# CM4_Conn.net
KiCad netlist of a schematic drawn in Altium Designer
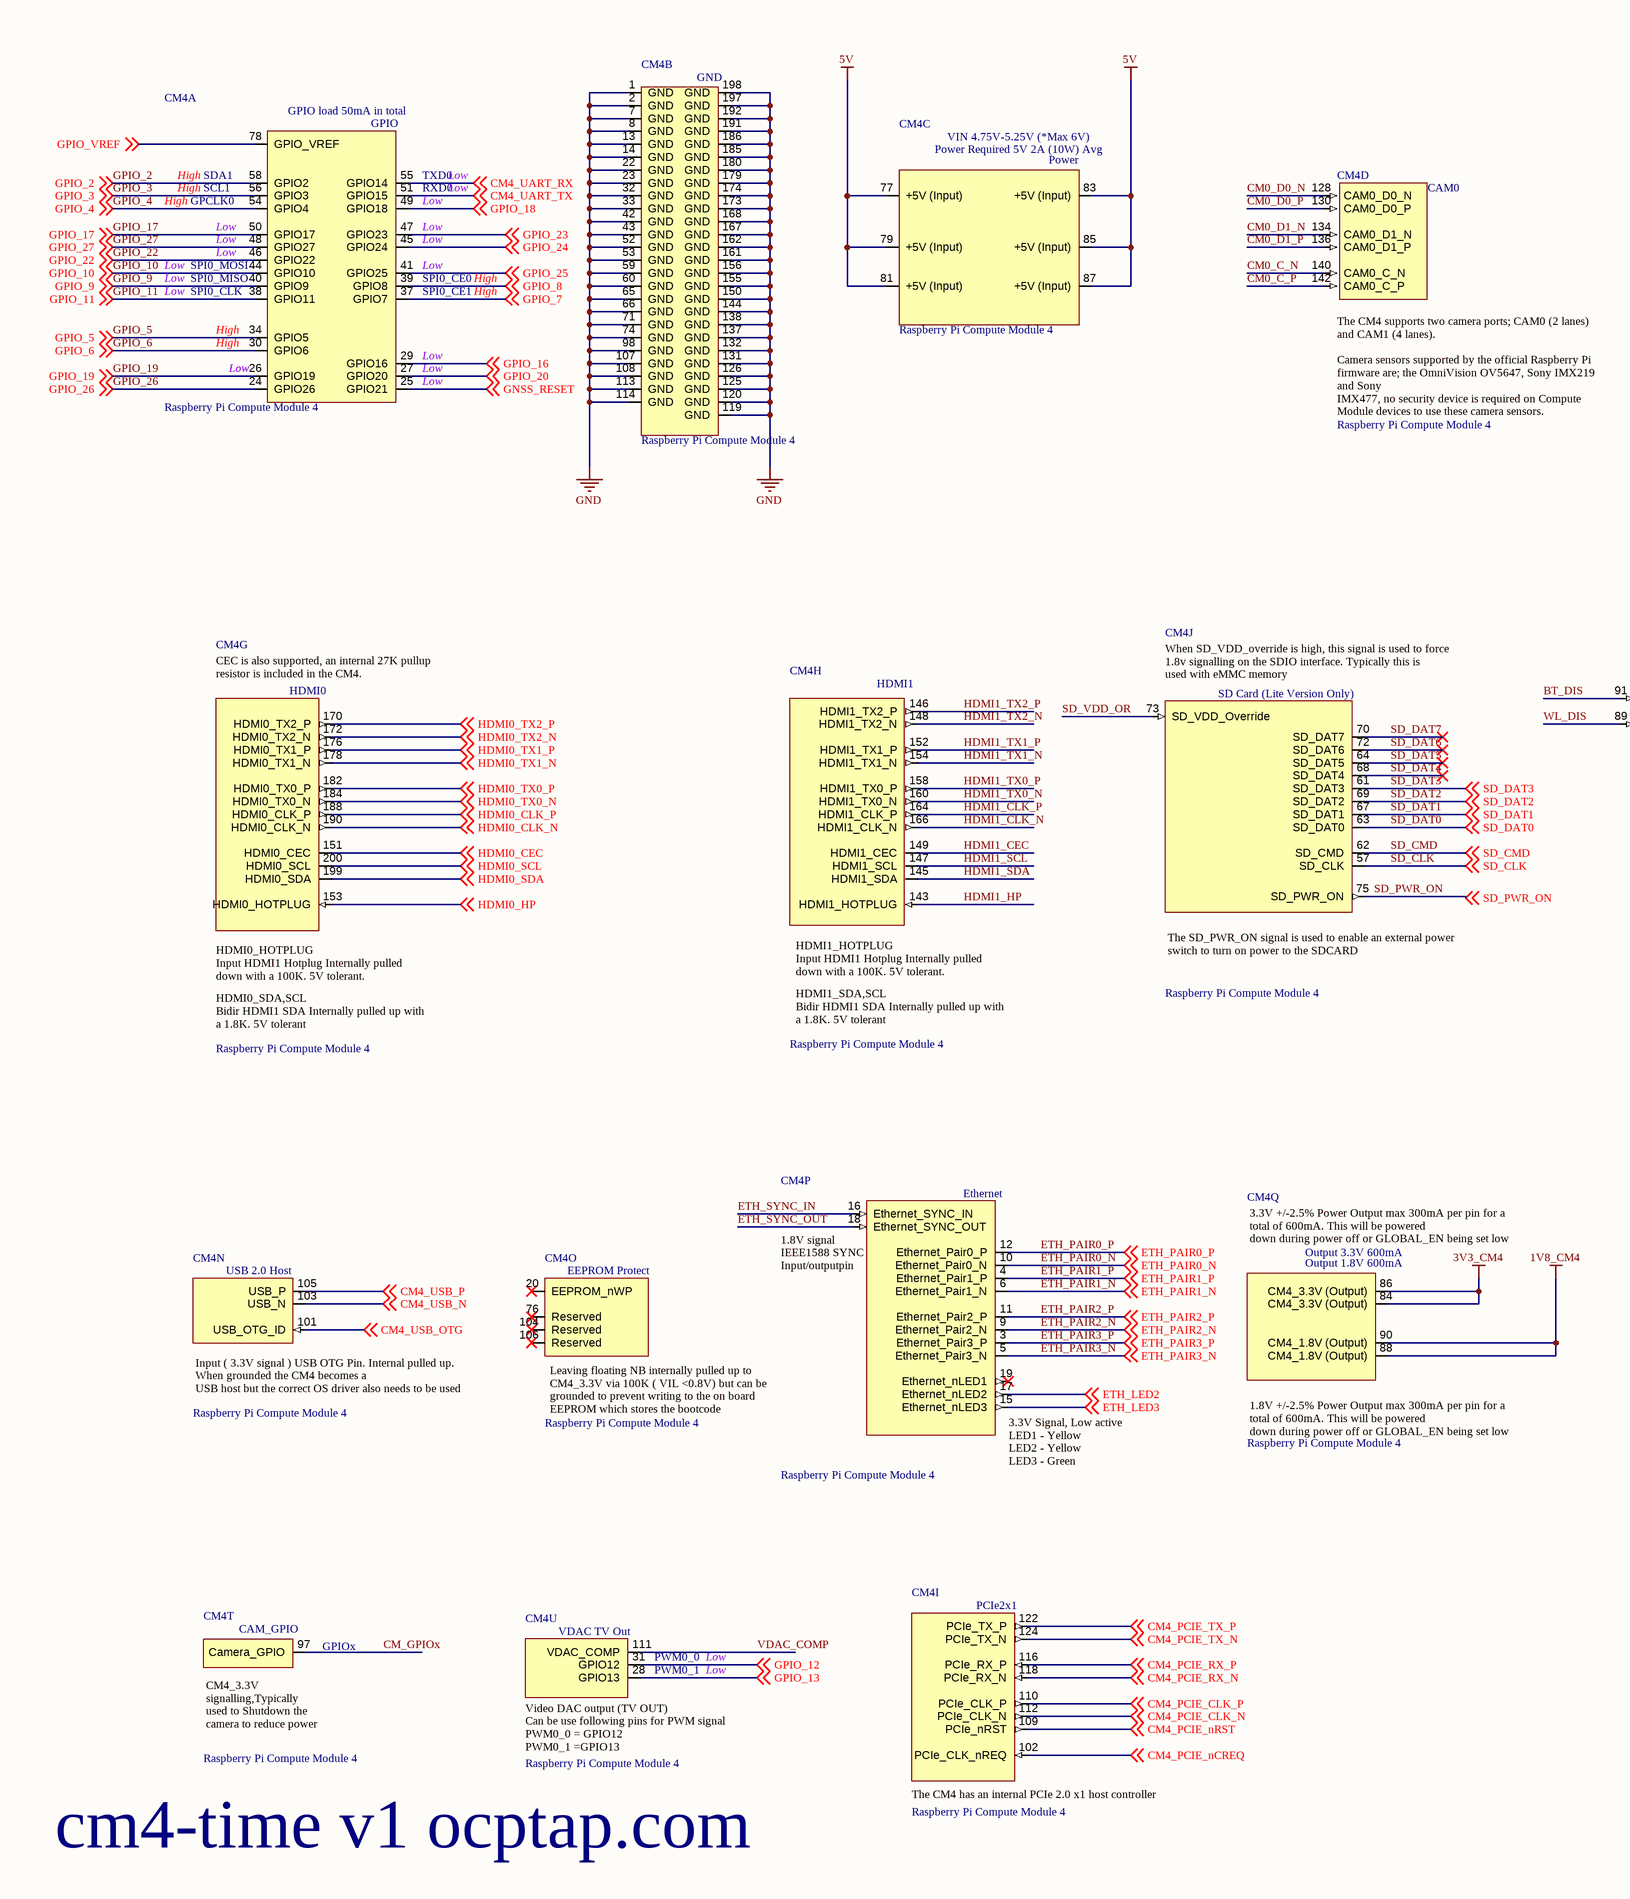
[diagram p0: CM4_Conn.SchDoc, left]
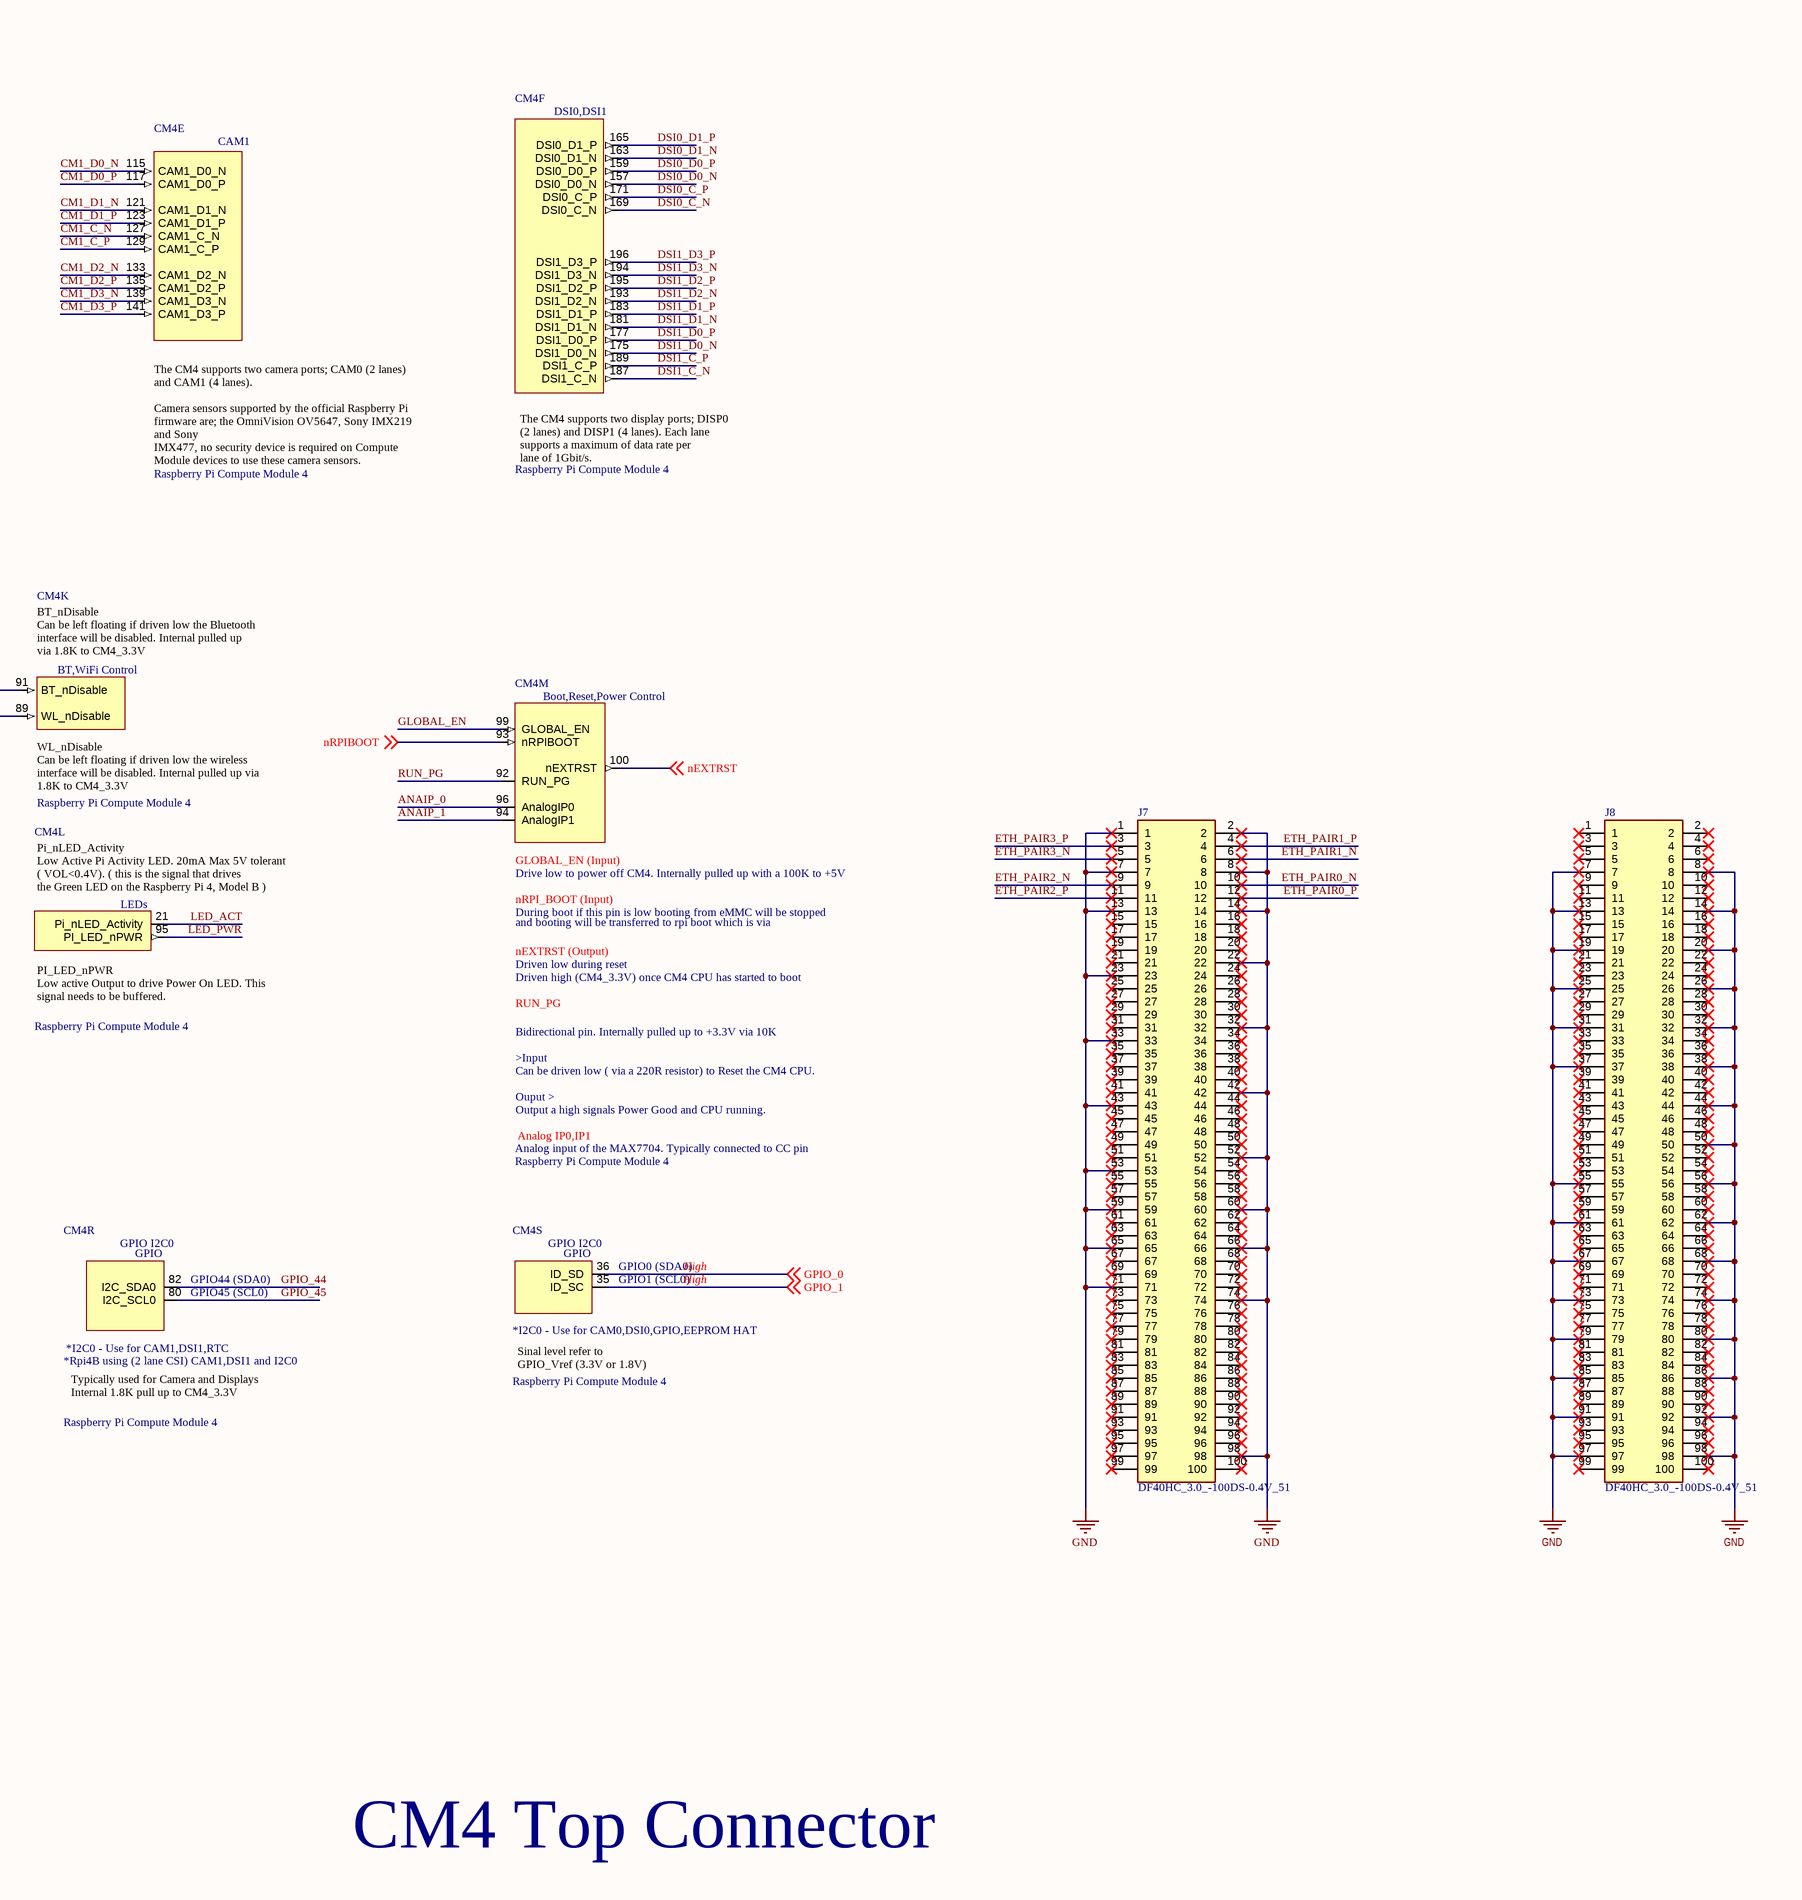
[diagram p1: CM4_Conn.SchDoc, right]

(export (version "E")
  (design (tool "Eeschema 10.0.6"))
  (components
    (comp (ref "CM4")
      (value "Raspberry Pi Compute Module 4")
      (footprint "CM4-F40C-100DS-0.4v_1.5mm_0mm")
      (description "Raspberry Pi Compute Module 4 by Amornthep Phunsin")
      (libsource (lib "CM4") (part "CM4"))
    )
    (comp (ref "J7")
      (value "DF40HC_3.0_-100DS-0.4V_51")
      (footprint "DF40HC30100DS04V51")
      (description "Connector")
      (fields
        (field (name "MANUFACTURER_PART_NUMBER") "DF40HC(3.0)-100DS-0.4V(51")
        (field (name "MOUSER PART NUMBER") "798-DF40HC30100DS451")
      )
      (libsource (lib "SamacSys") (part "DF40HC_3.0_-100DS-0.4V_51"))
    )
    (comp (ref "J8")
      (value "DF40HC_3.0_-100DS-0.4V_51")
      (footprint "DF40HC30100DS04V51")
      (description "Connector")
      (fields
        (field (name "MANUFACTURER_PART_NUMBER") "DF40HC(3.0)-100DS-0.4V(51")
        (field (name "MOUSER PART NUMBER") "798-DF40HC30100DS451")
      )
      (libsource (lib "SamacSys") (part "DF40HC_3.0_-100DS-0.4V_51"))
    )
  )
  (nets
    (net (code "1") (name "/ANAIP_0") (class "Default")
      (node (ref "CM4") (pin "96") (pinfunction "AnalogIP0_96") (pintype "passive"))
    )
    (net (code "2") (name "/ANAIP_1") (class "Default")
      (node (ref "CM4") (pin "94") (pinfunction "AnalogIP1_94") (pintype "passive"))
    )
    (net (code "3") (name "/BT_DIS") (class "Default")
      (node (ref "CM4") (pin "91") (pinfunction "BT_nDisable_91") (pintype "input"))
    )
    (net (code "4") (name "/CM0_C_N") (class "Default")
      (node (ref "CM4") (pin "140") (pinfunction "CAM0_C_N_140") (pintype "input"))
    )
    (net (code "5") (name "/CM0_C_P") (class "Default")
      (node (ref "CM4") (pin "142") (pinfunction "CAM0_C_P_142") (pintype "input"))
    )
    (net (code "6") (name "/CM0_D0_N") (class "Default")
      (node (ref "CM4") (pin "128") (pinfunction "CAM0_D0_N_128") (pintype "input"))
    )
    (net (code "7") (name "/CM0_D0_P") (class "Default")
      (node (ref "CM4") (pin "130") (pinfunction "CAM0_D0_P_130") (pintype "input"))
    )
    (net (code "8") (name "/CM0_D1_N") (class "Default")
      (node (ref "CM4") (pin "134") (pinfunction "CAM0_D1_N_134") (pintype "input"))
    )
    (net (code "9") (name "/CM0_D1_P") (class "Default")
      (node (ref "CM4") (pin "136") (pinfunction "CAM0_D1_P_136") (pintype "input"))
    )
    (net (code "10") (name "/CM1_C_N") (class "Default")
      (node (ref "CM4") (pin "127") (pinfunction "CAM1_C_N_127") (pintype "input"))
    )
    (net (code "11") (name "/CM1_C_P") (class "Default")
      (node (ref "CM4") (pin "129") (pinfunction "CAM1_C_P_129") (pintype "input"))
    )
    (net (code "12") (name "/CM1_D0_N") (class "Default")
      (node (ref "CM4") (pin "115") (pinfunction "CAM1_D0_N_115") (pintype "input"))
    )
    (net (code "13") (name "/CM1_D0_P") (class "Default")
      (node (ref "CM4") (pin "117") (pinfunction "CAM1_D0_P_117") (pintype "input"))
    )
    (net (code "14") (name "/CM1_D1_N") (class "Default")
      (node (ref "CM4") (pin "121") (pinfunction "CAM1_D1_N_121") (pintype "input"))
    )
    (net (code "15") (name "/CM1_D1_P") (class "Default")
      (node (ref "CM4") (pin "123") (pinfunction "CAM1_D1_P_123") (pintype "input"))
    )
    (net (code "16") (name "/CM1_D2_N") (class "Default")
      (node (ref "CM4") (pin "133") (pinfunction "CAM1_D2_N_133") (pintype "input"))
    )
    (net (code "17") (name "/CM1_D2_P") (class "Default")
      (node (ref "CM4") (pin "135") (pinfunction "CAM1_D2_P_135") (pintype "input"))
    )
    (net (code "18") (name "/CM1_D3_N") (class "Default")
      (node (ref "CM4") (pin "139") (pinfunction "CAM1_D3_N_139") (pintype "input"))
    )
    (net (code "19") (name "/CM1_D3_P") (class "Default")
      (node (ref "CM4") (pin "141") (pinfunction "CAM1_D3_P_141") (pintype "input"))
    )
    (net (code "20") (name "/CM_GPIOx") (class "Default")
      (node (ref "CM4") (pin "97") (pinfunction "Camera_GPIO_97") (pintype "passive"))
    )
    (net (code "21") (name "/DSI0_C_N") (class "Default")
      (node (ref "CM4") (pin "169") (pinfunction "DSI0_C_N_169") (pintype "output"))
    )
    (net (code "22") (name "/DSI0_C_P") (class "Default")
      (node (ref "CM4") (pin "171") (pinfunction "DSI0_C_P_171") (pintype "output"))
    )
    (net (code "23") (name "/DSI0_D0_N") (class "Default")
      (node (ref "CM4") (pin "157") (pinfunction "DSI0_D0_N_157") (pintype "output"))
    )
    (net (code "24") (name "/DSI0_D0_P") (class "Default")
      (node (ref "CM4") (pin "159") (pinfunction "DSI0_D0_P_159") (pintype "output"))
    )
    (net (code "25") (name "/DSI0_D1_N") (class "Default")
      (node (ref "CM4") (pin "163") (pinfunction "DSI0_D1_N_163") (pintype "output"))
    )
    (net (code "26") (name "/DSI0_D1_P") (class "Default")
      (node (ref "CM4") (pin "165") (pinfunction "DSI0_D1_P_165") (pintype "output"))
    )
    (net (code "27") (name "/DSI1_C_N") (class "Default")
      (node (ref "CM4") (pin "187") (pinfunction "DSI1_C_N_187") (pintype "output"))
    )
    (net (code "28") (name "/DSI1_C_P") (class "Default")
      (node (ref "CM4") (pin "189") (pinfunction "DSI1_C_P_189") (pintype "output"))
    )
    (net (code "29") (name "/DSI1_D0_N") (class "Default")
      (node (ref "CM4") (pin "175") (pinfunction "DSI1_D0_N_175") (pintype "output"))
    )
    (net (code "30") (name "/DSI1_D0_P") (class "Default")
      (node (ref "CM4") (pin "177") (pinfunction "DSI1_D0_P_177") (pintype "output"))
    )
    (net (code "31") (name "/DSI1_D1_N") (class "Default")
      (node (ref "CM4") (pin "181") (pinfunction "DSI1_D1_N_181") (pintype "output"))
    )
    (net (code "32") (name "/DSI1_D1_P") (class "Default")
      (node (ref "CM4") (pin "183") (pinfunction "DSI1_D1_P_183") (pintype "output"))
    )
    (net (code "33") (name "/DSI1_D2_N") (class "Default")
      (node (ref "CM4") (pin "193") (pinfunction "DSI1_D2_N_193") (pintype "output"))
    )
    (net (code "34") (name "/DSI1_D2_P") (class "Default")
      (node (ref "CM4") (pin "195") (pinfunction "DSI1_D2_P_195") (pintype "output"))
    )
    (net (code "35") (name "/DSI1_D3_N") (class "Default")
      (node (ref "CM4") (pin "194") (pinfunction "DSI1_D3_N_194") (pintype "output"))
    )
    (net (code "36") (name "/DSI1_D3_P") (class "Default")
      (node (ref "CM4") (pin "196") (pinfunction "DSI1_D3_P_196") (pintype "output"))
    )
    (net (code "37") (name "/ETH_SYNC_IN") (class "Default")
      (node (ref "CM4") (pin "16") (pinfunction "Ethernet_SYNC_IN_16") (pintype "input"))
    )
    (net (code "38") (name "/ETH_SYNC_OUT") (class "Default")
      (node (ref "CM4") (pin "18") (pinfunction "Ethernet_SYNC_OUT_18") (pintype "input"))
    )
    (net (code "39") (name "/GLOBAL_EN") (class "Default")
      (node (ref "CM4") (pin "99") (pinfunction "GLOBAL_EN_99") (pintype "input"))
    )
    (net (code "40") (name "/GPIO_44") (class "Default")
      (node (ref "CM4") (pin "82") (pinfunction "I2C_SDA0_82") (pintype "passive"))
    )
    (net (code "41") (name "/GPIO_45") (class "Default")
      (node (ref "CM4") (pin "80") (pinfunction "I2C_SCL0_80") (pintype "passive"))
    )
    (net (code "42") (name "/HDMI1_CEC") (class "Default")
      (node (ref "CM4") (pin "149") (pinfunction "HDMI1_CEC_149") (pintype "open_collector"))
    )
    (net (code "43") (name "/HDMI1_CLK_N") (class "Default")
      (node (ref "CM4") (pin "166") (pinfunction "HDMI1_CLK_N_166") (pintype "output"))
    )
    (net (code "44") (name "/HDMI1_CLK_P") (class "Default")
      (node (ref "CM4") (pin "164") (pinfunction "HDMI1_CLK_P_164") (pintype "output"))
    )
    (net (code "45") (name "/HDMI1_HP") (class "Default")
      (node (ref "CM4") (pin "143") (pinfunction "HDMI1_HOTPLUG_143") (pintype "input"))
    )
    (net (code "46") (name "/HDMI1_SCL") (class "Default")
      (node (ref "CM4") (pin "147") (pinfunction "HDMI1_SCL_147") (pintype "open_collector"))
    )
    (net (code "47") (name "/HDMI1_SDA") (class "Default")
      (node (ref "CM4") (pin "145") (pinfunction "HDMI1_SDA_145") (pintype "bidirectional"))
    )
    (net (code "48") (name "/HDMI1_TX0_N") (class "Default")
      (node (ref "CM4") (pin "160") (pinfunction "HDMI1_TX0_N_160") (pintype "output"))
    )
    (net (code "49") (name "/HDMI1_TX0_P") (class "Default")
      (node (ref "CM4") (pin "158") (pinfunction "HDMI1_TX0_P_158") (pintype "output"))
    )
    (net (code "50") (name "/HDMI1_TX1_N") (class "Default")
      (node (ref "CM4") (pin "154") (pinfunction "HDMI1_TX1_N_154") (pintype "output"))
    )
    (net (code "51") (name "/HDMI1_TX1_P") (class "Default")
      (node (ref "CM4") (pin "152") (pinfunction "HDMI1_TX1_P_152") (pintype "output"))
    )
    (net (code "52") (name "/HDMI1_TX2_N") (class "Default")
      (node (ref "CM4") (pin "148") (pinfunction "HDMI1_TX2_N_148") (pintype "output"))
    )
    (net (code "53") (name "/HDMI1_TX2_P") (class "Default")
      (node (ref "CM4") (pin "146") (pinfunction "HDMI1_TX2_P_146") (pintype "output"))
    )
    (net (code "54") (name "/LED_ACT") (class "Default")
      (node (ref "CM4") (pin "21") (pinfunction "Pi_nLED_Activity_21") (pintype "open_collector"))
    )
    (net (code "55") (name "/LED_PWR") (class "Default")
      (node (ref "CM4") (pin "95") (pinfunction "PI_LED_nPWR_95") (pintype "output"))
    )
    (net (code "56") (name "/RUN_PG") (class "Default")
      (node (ref "CM4") (pin "92") (pinfunction "RUN_PG_92") (pintype "passive"))
    )
    (net (code "57") (name "/SD_DAT4") (class "Default")
      (node (ref "CM4") (pin "68") (pinfunction "SD_DAT4_68") (pintype "passive+no_connect"))
    )
    (net (code "58") (name "/SD_DAT5") (class "Default")
      (node (ref "CM4") (pin "64") (pinfunction "SD_DAT5_64") (pintype "passive+no_connect"))
    )
    (net (code "59") (name "/SD_DAT6") (class "Default")
      (node (ref "CM4") (pin "72") (pinfunction "SD_DAT6_72") (pintype "passive+no_connect"))
    )
    (net (code "60") (name "/SD_DAT7") (class "Default")
      (node (ref "CM4") (pin "70") (pinfunction "SD_DAT7_70") (pintype "passive+no_connect"))
    )
    (net (code "61") (name "/SD_VDD_OR") (class "Default")
      (node (ref "CM4") (pin "73") (pinfunction "SD_VDD_Override_73") (pintype "input"))
    )
    (net (code "62") (name "/VDAC_COMP") (class "Default")
      (node (ref "CM4") (pin "111") (pinfunction "VDAC_COMP_111") (pintype "passive"))
    )
    (net (code "63") (name "/WL_DIS") (class "Default")
      (node (ref "CM4") (pin "89") (pinfunction "WL_nDisable_89") (pintype "input"))
    )
    (net (code "64") (name "1V8_CM4") (class "Default")
      (node (ref "CM4") (pin "88") (pinfunction "CM4_1.8V_(Output)_88") (pintype "power_in"))
      (node (ref "CM4") (pin "90") (pinfunction "CM4_1.8V_(Output)_90") (pintype "power_in"))
    )
    (net (code "65") (name "3V3_CM4") (class "Default")
      (node (ref "CM4") (pin "84") (pinfunction "CM4_3.3V_(Output)_84") (pintype "power_in"))
      (node (ref "CM4") (pin "86") (pinfunction "CM4_3.3V_(Output)_86") (pintype "power_in"))
    )
    (net (code "66") (name "5V") (class "Default")
      (node (ref "CM4") (pin "77") (pinfunction "+5V_(Input)_77") (pintype "power_in"))
      (node (ref "CM4") (pin "79") (pinfunction "+5V_(Input)_79") (pintype "power_in"))
      (node (ref "CM4") (pin "81") (pinfunction "+5V_(Input)_81") (pintype "power_in"))
      (node (ref "CM4") (pin "83") (pinfunction "+5V_(Input)_83") (pintype "power_in"))
      (node (ref "CM4") (pin "85") (pinfunction "+5V_(Input)_85") (pintype "power_in"))
      (node (ref "CM4") (pin "87") (pinfunction "+5V_(Input)_87") (pintype "power_in"))
    )
    (net (code "67") (name "CM4_PCIE_CLK_N") (class "Default")
      (node (ref "CM4") (pin "112") (pinfunction "PCIe_CLK_N_112") (pintype "output"))
    )
    (net (code "68") (name "CM4_PCIE_CLK_P") (class "Default")
      (node (ref "CM4") (pin "110") (pinfunction "PCIe_CLK_P_110") (pintype "output"))
    )
    (net (code "69") (name "CM4_PCIE_RX_N") (class "Default")
      (node (ref "CM4") (pin "118") (pinfunction "PCIe_RX_N_118") (pintype "input"))
    )
    (net (code "70") (name "CM4_PCIE_RX_P") (class "Default")
      (node (ref "CM4") (pin "116") (pinfunction "PCIe_RX_P_116") (pintype "input"))
    )
    (net (code "71") (name "CM4_PCIE_TX_N") (class "Default")
      (node (ref "CM4") (pin "124") (pinfunction "PCIe_TX_N_124") (pintype "output"))
    )
    (net (code "72") (name "CM4_PCIE_TX_P") (class "Default")
      (node (ref "CM4") (pin "122") (pinfunction "PCIe_TX_P_122") (pintype "output"))
    )
    (net (code "73") (name "CM4_PCIE_nCREQ") (class "Default")
      (node (ref "CM4") (pin "102") (pinfunction "PCIe_CLK_nREQ_102") (pintype "input"))
    )
    (net (code "74") (name "CM4_PCIE_nRST") (class "Default")
      (node (ref "CM4") (pin "109") (pinfunction "PCIe_nRST_109") (pintype "output"))
    )
    (net (code "75") (name "CM4_UART_RX") (class "Default")
      (node (ref "CM4") (pin "55") (pinfunction "GPIO14_55") (pintype "passive"))
    )
    (net (code "76") (name "CM4_UART_TX") (class "Default")
      (node (ref "CM4") (pin "51") (pinfunction "GPIO15_51") (pintype "passive"))
    )
    (net (code "77") (name "CM4_USB_N") (class "Default")
      (node (ref "CM4") (pin "103") (pinfunction "USB_N_103") (pintype "passive"))
    )
    (net (code "78") (name "CM4_USB_OTG") (class "Default")
      (node (ref "CM4") (pin "101") (pinfunction "USB_OTG_ID_101") (pintype "input"))
    )
    (net (code "79") (name "CM4_USB_P") (class "Default")
      (node (ref "CM4") (pin "105") (pinfunction "USB_P_105") (pintype "passive"))
    )
    (net (code "80") (name "ETH_LED2") (class "Default")
      (node (ref "CM4") (pin "17") (pinfunction "Ethernet_nLED2_17") (pintype "output"))
    )
    (net (code "81") (name "ETH_LED3") (class "Default")
      (node (ref "CM4") (pin "15") (pinfunction "Ethernet_nLED3_15") (pintype "output"))
    )
    (net (code "82") (name "ETH_PAIR0_N") (class "Default")
      (node (ref "CM4") (pin "10") (pinfunction "Ethernet_Pair0_N_10") (pintype "passive"))
      (node (ref "J7") (pin "10") (pinfunction "10_10") (pintype "passive"))
    )
    (net (code "83") (name "ETH_PAIR0_P") (class "Default")
      (node (ref "CM4") (pin "12") (pinfunction "Ethernet_Pair0_P_12") (pintype "passive"))
      (node (ref "J7") (pin "12") (pinfunction "12_12") (pintype "passive"))
    )
    (net (code "84") (name "ETH_PAIR1_N") (class "Default")
      (node (ref "CM4") (pin "6") (pinfunction "Ethernet_Pair1_N_6") (pintype "passive"))
      (node (ref "J7") (pin "6") (pinfunction "6_6") (pintype "passive"))
    )
    (net (code "85") (name "ETH_PAIR1_P") (class "Default")
      (node (ref "CM4") (pin "4") (pinfunction "Ethernet_Pair1_P_4") (pintype "passive"))
      (node (ref "J7") (pin "4") (pinfunction "4_4") (pintype "passive"))
    )
    (net (code "86") (name "ETH_PAIR2_N") (class "Default")
      (node (ref "CM4") (pin "9") (pinfunction "Ethernet_Pair2_N_9") (pintype "passive"))
      (node (ref "J7") (pin "9") (pinfunction "9_9") (pintype "passive"))
    )
    (net (code "87") (name "ETH_PAIR2_P") (class "Default")
      (node (ref "CM4") (pin "11") (pinfunction "Ethernet_Pair2_P_11") (pintype "passive"))
      (node (ref "J7") (pin "11") (pinfunction "11_11") (pintype "passive"))
    )
    (net (code "88") (name "ETH_PAIR3_N") (class "Default")
      (node (ref "CM4") (pin "5") (pinfunction "Ethernet_Pair3_N_5") (pintype "passive"))
      (node (ref "J7") (pin "5") (pinfunction "5_5") (pintype "passive"))
    )
    (net (code "89") (name "ETH_PAIR3_P") (class "Default")
      (node (ref "CM4") (pin "3") (pinfunction "Ethernet_Pair3_P_3") (pintype "passive"))
      (node (ref "J7") (pin "3") (pinfunction "3_3") (pintype "passive"))
    )
    (net (code "90") (name "GND") (class "Default")
      (node (ref "CM4") (pin "1") (pinfunction "GND_1") (pintype "power_in"))
      (node (ref "CM4") (pin "107") (pinfunction "GND_107") (pintype "power_in"))
      (node (ref "CM4") (pin "108") (pinfunction "GND_108") (pintype "power_in"))
      (node (ref "CM4") (pin "113") (pinfunction "GND_113") (pintype "power_in"))
      (node (ref "CM4") (pin "114") (pinfunction "GND_114") (pintype "power_in"))
      (node (ref "CM4") (pin "119") (pinfunction "GND_119") (pintype "power_in"))
      (node (ref "CM4") (pin "120") (pinfunction "GND_120") (pintype "power_in"))
      (node (ref "CM4") (pin "125") (pinfunction "GND_125") (pintype "power_in"))
      (node (ref "CM4") (pin "126") (pinfunction "GND_126") (pintype "power_in"))
      (node (ref "CM4") (pin "13") (pinfunction "GND_13") (pintype "power_in"))
      (node (ref "CM4") (pin "131") (pinfunction "GND_131") (pintype "power_in"))
      (node (ref "CM4") (pin "132") (pinfunction "GND_132") (pintype "power_in"))
      (node (ref "CM4") (pin "137") (pinfunction "GND_137") (pintype "power_in"))
      (node (ref "CM4") (pin "138") (pinfunction "GND_138") (pintype "power_in"))
      (node (ref "CM4") (pin "14") (pinfunction "GND_14") (pintype "power_in"))
      (node (ref "CM4") (pin "144") (pinfunction "GND_144") (pintype "power_in"))
      (node (ref "CM4") (pin "150") (pinfunction "GND_150") (pintype "power_in"))
      (node (ref "CM4") (pin "155") (pinfunction "GND_155") (pintype "power_in"))
      (node (ref "CM4") (pin "156") (pinfunction "GND_156") (pintype "power_in"))
      (node (ref "CM4") (pin "161") (pinfunction "GND_161") (pintype "power_in"))
      (node (ref "CM4") (pin "162") (pinfunction "GND_162") (pintype "power_in"))
      (node (ref "CM4") (pin "167") (pinfunction "GND_167") (pintype "power_in"))
      (node (ref "CM4") (pin "168") (pinfunction "GND_168") (pintype "power_in"))
      (node (ref "CM4") (pin "173") (pinfunction "GND_173") (pintype "power_in"))
      (node (ref "CM4") (pin "174") (pinfunction "GND_174") (pintype "power_in"))
      (node (ref "CM4") (pin "179") (pinfunction "GND_179") (pintype "power_in"))
      (node (ref "CM4") (pin "180") (pinfunction "GND_180") (pintype "power_in"))
      (node (ref "CM4") (pin "185") (pinfunction "GND_185") (pintype "power_in"))
      (node (ref "CM4") (pin "186") (pinfunction "GND_186") (pintype "power_in"))
      (node (ref "CM4") (pin "191") (pinfunction "GND_191") (pintype "power_in"))
      (node (ref "CM4") (pin "192") (pinfunction "GND_192") (pintype "power_in"))
      (node (ref "CM4") (pin "197") (pinfunction "GND_197") (pintype "power_in"))
      (node (ref "CM4") (pin "198") (pinfunction "GND_198") (pintype "power_in"))
      (node (ref "CM4") (pin "2") (pinfunction "GND_2") (pintype "power_in"))
      (node (ref "CM4") (pin "22") (pinfunction "GND_22") (pintype "power_in"))
      (node (ref "CM4") (pin "23") (pinfunction "GND_23") (pintype "power_in"))
      (node (ref "CM4") (pin "32") (pinfunction "GND_32") (pintype "power_in"))
      (node (ref "CM4") (pin "33") (pinfunction "GND_33") (pintype "power_in"))
      (node (ref "CM4") (pin "42") (pinfunction "GND_42") (pintype "power_in"))
      (node (ref "CM4") (pin "43") (pinfunction "GND_43") (pintype "power_in"))
      (node (ref "CM4") (pin "52") (pinfunction "GND_52") (pintype "power_in"))
      (node (ref "CM4") (pin "53") (pinfunction "GND_53") (pintype "power_in"))
      (node (ref "CM4") (pin "59") (pinfunction "GND_59") (pintype "power_in"))
      (node (ref "CM4") (pin "60") (pinfunction "GND_60") (pintype "power_in"))
      (node (ref "CM4") (pin "65") (pinfunction "GND_65") (pintype "power_in"))
      (node (ref "CM4") (pin "66") (pinfunction "GND_66") (pintype "power_in"))
      (node (ref "CM4") (pin "7") (pinfunction "GND_7") (pintype "power_in"))
      (node (ref "CM4") (pin "71") (pinfunction "GND_71") (pintype "power_in"))
      (node (ref "CM4") (pin "74") (pinfunction "GND_74") (pintype "power_in"))
      (node (ref "CM4") (pin "8") (pinfunction "GND_8") (pintype "power_in"))
      (node (ref "CM4") (pin "98") (pinfunction "GND_98") (pintype "power_in"))
      (node (ref "J7") (pin "1") (pinfunction "1_1") (pintype "passive"))
      (node (ref "J7") (pin "13") (pinfunction "13_13") (pintype "passive"))
      (node (ref "J7") (pin "14") (pinfunction "14_14") (pintype "passive"))
      (node (ref "J7") (pin "2") (pinfunction "2_2") (pintype "passive"))
      (node (ref "J7") (pin "22") (pinfunction "22_22") (pintype "passive"))
      (node (ref "J7") (pin "23") (pinfunction "23_23") (pintype "passive"))
      (node (ref "J7") (pin "32") (pinfunction "32_32") (pintype "passive"))
      (node (ref "J7") (pin "33") (pinfunction "33_33") (pintype "passive"))
      (node (ref "J7") (pin "42") (pinfunction "42_42") (pintype "passive"))
      (node (ref "J7") (pin "43") (pinfunction "43_43") (pintype "passive"))
      (node (ref "J7") (pin "52") (pinfunction "52_52") (pintype "passive"))
      (node (ref "J7") (pin "53") (pinfunction "53_53") (pintype "passive"))
      (node (ref "J7") (pin "59") (pinfunction "59_59") (pintype "passive"))
      (node (ref "J7") (pin "60") (pinfunction "60_60") (pintype "passive"))
      (node (ref "J7") (pin "65") (pinfunction "65_65") (pintype "passive"))
      (node (ref "J7") (pin "66") (pinfunction "66_66") (pintype "passive"))
      (node (ref "J7") (pin "7") (pinfunction "7_7") (pintype "passive"))
      (node (ref "J7") (pin "71") (pinfunction "71_71") (pintype "passive"))
      (node (ref "J7") (pin "74") (pinfunction "74_74") (pintype "passive"))
      (node (ref "J7") (pin "8") (pinfunction "8_8") (pintype "passive"))
      (node (ref "J7") (pin "98") (pinfunction "98_98") (pintype "passive"))
      (node (ref "J8") (pin "13") (pinfunction "13_13") (pintype "passive"))
      (node (ref "J8") (pin "14") (pinfunction "14_14") (pintype "passive"))
      (node (ref "J8") (pin "19") (pinfunction "19_19") (pintype "passive"))
      (node (ref "J8") (pin "20") (pinfunction "20_20") (pintype "passive"))
      (node (ref "J8") (pin "25") (pinfunction "25_25") (pintype "passive"))
      (node (ref "J8") (pin "26") (pinfunction "26_26") (pintype "passive"))
      (node (ref "J8") (pin "31") (pinfunction "31_31") (pintype "passive"))
      (node (ref "J8") (pin "32") (pinfunction "32_32") (pintype "passive"))
      (node (ref "J8") (pin "37") (pinfunction "37_37") (pintype "passive"))
      (node (ref "J8") (pin "38") (pinfunction "38_38") (pintype "passive"))
      (node (ref "J8") (pin "44") (pinfunction "44_44") (pintype "passive"))
      (node (ref "J8") (pin "50") (pinfunction "50_50") (pintype "passive"))
      (node (ref "J8") (pin "55") (pinfunction "55_55") (pintype "passive"))
      (node (ref "J8") (pin "56") (pinfunction "56_56") (pintype "passive"))
      (node (ref "J8") (pin "61") (pinfunction "61_61") (pintype "passive"))
      (node (ref "J8") (pin "62") (pinfunction "62_62") (pintype "passive"))
      (node (ref "J8") (pin "67") (pinfunction "67_67") (pintype "passive"))
      (node (ref "J8") (pin "68") (pinfunction "68_68") (pintype "passive"))
      (node (ref "J8") (pin "7") (pinfunction "7_7") (pintype "passive"))
      (node (ref "J8") (pin "73") (pinfunction "73_73") (pintype "passive"))
      (node (ref "J8") (pin "74") (pinfunction "74_74") (pintype "passive"))
      (node (ref "J8") (pin "79") (pinfunction "79_79") (pintype "passive"))
      (node (ref "J8") (pin "8") (pinfunction "8_8") (pintype "passive"))
      (node (ref "J8") (pin "80") (pinfunction "80_80") (pintype "passive"))
      (node (ref "J8") (pin "85") (pinfunction "85_85") (pintype "passive"))
      (node (ref "J8") (pin "86") (pinfunction "86_86") (pintype "passive"))
      (node (ref "J8") (pin "91") (pinfunction "91_91") (pintype "passive"))
      (node (ref "J8") (pin "92") (pinfunction "92_92") (pintype "passive"))
      (node (ref "J8") (pin "97") (pinfunction "97_97") (pintype "passive"))
      (node (ref "J8") (pin "98") (pinfunction "98_98") (pintype "passive"))
    )
    (net (code "91") (name "GNSS_RESET") (class "Default")
      (node (ref "CM4") (pin "25") (pinfunction "GPIO21_25") (pintype "passive"))
    )
    (net (code "92") (name "GPIO_0") (class "Default")
      (node (ref "CM4") (pin "36") (pinfunction "ID_SD_36") (pintype "passive"))
    )
    (net (code "93") (name "GPIO_1") (class "Default")
      (node (ref "CM4") (pin "35") (pinfunction "ID_SC_35") (pintype "passive"))
    )
    (net (code "94") (name "GPIO_2") (class "Default")
      (node (ref "CM4") (pin "58") (pinfunction "GPIO2_58") (pintype "passive"))
    )
    (net (code "95") (name "GPIO_3") (class "Default")
      (node (ref "CM4") (pin "56") (pinfunction "GPIO3_56") (pintype "passive"))
    )
    (net (code "96") (name "GPIO_4") (class "Default")
      (node (ref "CM4") (pin "54") (pinfunction "GPIO4_54") (pintype "passive"))
    )
    (net (code "97") (name "GPIO_5") (class "Default")
      (node (ref "CM4") (pin "34") (pinfunction "GPIO5_34") (pintype "passive"))
    )
    (net (code "98") (name "GPIO_6") (class "Default")
      (node (ref "CM4") (pin "30") (pinfunction "GPIO6_30") (pintype "passive"))
    )
    (net (code "99") (name "GPIO_7") (class "Default")
      (node (ref "CM4") (pin "37") (pinfunction "GPIO7_37") (pintype "passive"))
    )
    (net (code "100") (name "GPIO_8") (class "Default")
      (node (ref "CM4") (pin "39") (pinfunction "GPIO8_39") (pintype "passive"))
    )
    (net (code "101") (name "GPIO_9") (class "Default")
      (node (ref "CM4") (pin "40") (pinfunction "GPIO9_40") (pintype "passive"))
    )
    (net (code "102") (name "GPIO_10") (class "Default")
      (node (ref "CM4") (pin "44") (pinfunction "GPIO10_44") (pintype "passive"))
    )
    (net (code "103") (name "GPIO_11") (class "Default")
      (node (ref "CM4") (pin "38") (pinfunction "GPIO11_38") (pintype "passive"))
    )
    (net (code "104") (name "GPIO_12") (class "Default")
      (node (ref "CM4") (pin "31") (pinfunction "GPIO12_31") (pintype "passive"))
    )
    (net (code "105") (name "GPIO_13") (class "Default")
      (node (ref "CM4") (pin "28") (pinfunction "GPIO13_28") (pintype "passive"))
    )
    (net (code "106") (name "GPIO_16") (class "Default")
      (node (ref "CM4") (pin "29") (pinfunction "GPIO16_29") (pintype "passive"))
    )
    (net (code "107") (name "GPIO_17") (class "Default")
      (node (ref "CM4") (pin "50") (pinfunction "GPIO17_50") (pintype "passive"))
    )
    (net (code "108") (name "GPIO_18") (class "Default")
      (node (ref "CM4") (pin "49") (pinfunction "GPIO18_49") (pintype "passive"))
    )
    (net (code "109") (name "GPIO_19") (class "Default")
      (node (ref "CM4") (pin "26") (pinfunction "GPIO19_26") (pintype "passive"))
    )
    (net (code "110") (name "GPIO_20") (class "Default")
      (node (ref "CM4") (pin "27") (pinfunction "GPIO20_27") (pintype "passive"))
    )
    (net (code "111") (name "GPIO_22") (class "Default")
      (node (ref "CM4") (pin "46") (pinfunction "GPIO22_46") (pintype "passive"))
    )
    (net (code "112") (name "GPIO_23") (class "Default")
      (node (ref "CM4") (pin "47") (pinfunction "GPIO23_47") (pintype "passive"))
    )
    (net (code "113") (name "GPIO_24") (class "Default")
      (node (ref "CM4") (pin "45") (pinfunction "GPIO24_45") (pintype "passive"))
    )
    (net (code "114") (name "GPIO_25") (class "Default")
      (node (ref "CM4") (pin "41") (pinfunction "GPIO25_41") (pintype "passive"))
    )
    (net (code "115") (name "GPIO_26") (class "Default")
      (node (ref "CM4") (pin "24") (pinfunction "GPIO26_24") (pintype "passive"))
    )
    (net (code "116") (name "GPIO_27") (class "Default")
      (node (ref "CM4") (pin "48") (pinfunction "GPIO27_48") (pintype "passive"))
    )
    (net (code "117") (name "GPIO_VREF") (class "Default")
      (node (ref "CM4") (pin "78") (pinfunction "GPIO_VREF_78") (pintype "power_in"))
    )
    (net (code "118") (name "HDMI0_CEC") (class "Default")
      (node (ref "CM4") (pin "151") (pinfunction "HDMI0_CEC_151") (pintype "open_collector"))
    )
    (net (code "119") (name "HDMI0_CLK_N") (class "Default")
      (node (ref "CM4") (pin "190") (pinfunction "HDMI0_CLK_N_190") (pintype "output"))
    )
    (net (code "120") (name "HDMI0_CLK_P") (class "Default")
      (node (ref "CM4") (pin "188") (pinfunction "HDMI0_CLK_P_188") (pintype "output"))
    )
    (net (code "121") (name "HDMI0_HP") (class "Default")
      (node (ref "CM4") (pin "153") (pinfunction "HDMI0_HOTPLUG_153") (pintype "input"))
    )
    (net (code "122") (name "HDMI0_SCL") (class "Default")
      (node (ref "CM4") (pin "200") (pinfunction "HDMI0_SCL_200") (pintype "open_collector"))
    )
    (net (code "123") (name "HDMI0_SDA") (class "Default")
      (node (ref "CM4") (pin "199") (pinfunction "HDMI0_SDA_199") (pintype "bidirectional"))
    )
    (net (code "124") (name "HDMI0_TX0_N") (class "Default")
      (node (ref "CM4") (pin "184") (pinfunction "HDMI0_TX0_N_184") (pintype "output"))
    )
    (net (code "125") (name "HDMI0_TX0_P") (class "Default")
      (node (ref "CM4") (pin "182") (pinfunction "HDMI0_TX0_P_182") (pintype "output"))
    )
    (net (code "126") (name "HDMI0_TX1_N") (class "Default")
      (node (ref "CM4") (pin "178") (pinfunction "HDMI0_TX1_N_178") (pintype "output"))
    )
    (net (code "127") (name "HDMI0_TX1_P") (class "Default")
      (node (ref "CM4") (pin "176") (pinfunction "HDMI0_TX1_P_176") (pintype "output"))
    )
    (net (code "128") (name "HDMI0_TX2_N") (class "Default")
      (node (ref "CM4") (pin "172") (pinfunction "HDMI0_TX2_N_172") (pintype "output"))
    )
    (net (code "129") (name "HDMI0_TX2_P") (class "Default")
      (node (ref "CM4") (pin "170") (pinfunction "HDMI0_TX2_P_170") (pintype "output"))
    )
    (net (code "130") (name "SD_CLK") (class "Default")
      (node (ref "CM4") (pin "57") (pinfunction "SD_CLK_57") (pintype "passive"))
    )
    (net (code "131") (name "SD_CMD") (class "Default")
      (node (ref "CM4") (pin "62") (pinfunction "SD_CMD_62") (pintype "passive"))
    )
    (net (code "132") (name "SD_DAT0") (class "Default")
      (node (ref "CM4") (pin "63") (pinfunction "SD_DAT0_63") (pintype "passive"))
    )
    (net (code "133") (name "SD_DAT1") (class "Default")
      (node (ref "CM4") (pin "67") (pinfunction "SD_DAT1_67") (pintype "passive"))
    )
    (net (code "134") (name "SD_DAT2") (class "Default")
      (node (ref "CM4") (pin "69") (pinfunction "SD_DAT2_69") (pintype "passive"))
    )
    (net (code "135") (name "SD_DAT3") (class "Default")
      (node (ref "CM4") (pin "61") (pinfunction "SD_DAT3_61") (pintype "passive"))
    )
    (net (code "136") (name "SD_PWR_ON") (class "Default")
      (node (ref "CM4") (pin "75") (pinfunction "SD_PWR_ON_75") (pintype "output"))
    )
    (net (code "137") (name "nEXTRST") (class "Default")
      (node (ref "CM4") (pin "100") (pinfunction "nEXTRST_100") (pintype "output"))
    )
    (net (code "138") (name "nRPIBOOT") (class "Default")
      (node (ref "CM4") (pin "93") (pinfunction "nRPIBOOT_93") (pintype "input"))
    )
    (net (code "139") (name "unconnected-(CM4O-EEPROM_nWP-Pad20)") (class "Default")
      (node (ref "CM4") (pin "20") (pinfunction "EEPROM_nWP_20") (pintype "passive+no_connect"))
    )
    (net (code "140") (name "unconnected-(CM4O-Reserved-Pad76)") (class "Default")
      (node (ref "CM4") (pin "76") (pinfunction "Reserved_76") (pintype "passive+no_connect"))
    )
    (net (code "141") (name "unconnected-(CM4O-Reserved-Pad104)") (class "Default")
      (node (ref "CM4") (pin "104") (pinfunction "Reserved_104") (pintype "passive+no_connect"))
    )
    (net (code "142") (name "unconnected-(CM4O-Reserved-Pad106)") (class "Default")
      (node (ref "CM4") (pin "106") (pinfunction "Reserved_106") (pintype "passive+no_connect"))
    )
    (net (code "143") (name "unconnected-(CM4P-Ethernet_nLED1-Pad19)") (class "Default")
      (node (ref "CM4") (pin "19") (pinfunction "Ethernet_nLED1_19") (pintype "output+no_connect"))
    )
    (net (code "144") (name "unconnected-(J7-Pad15)") (class "Default")
      (node (ref "J7") (pin "15") (pinfunction "15_15") (pintype "passive+no_connect"))
    )
    (net (code "145") (name "unconnected-(J7-Pad16)") (class "Default")
      (node (ref "J7") (pin "16") (pinfunction "16_16") (pintype "passive+no_connect"))
    )
    (net (code "146") (name "unconnected-(J7-Pad17)") (class "Default")
      (node (ref "J7") (pin "17") (pinfunction "17_17") (pintype "passive+no_connect"))
    )
    (net (code "147") (name "unconnected-(J7-Pad18)") (class "Default")
      (node (ref "J7") (pin "18") (pinfunction "18_18") (pintype "passive+no_connect"))
    )
    (net (code "148") (name "unconnected-(J7-Pad19)") (class "Default")
      (node (ref "J7") (pin "19") (pinfunction "19_19") (pintype "passive+no_connect"))
    )
    (net (code "149") (name "unconnected-(J7-Pad20)") (class "Default")
      (node (ref "J7") (pin "20") (pinfunction "20_20") (pintype "passive+no_connect"))
    )
    (net (code "150") (name "unconnected-(J7-Pad21)") (class "Default")
      (node (ref "J7") (pin "21") (pinfunction "21_21") (pintype "passive+no_connect"))
    )
    (net (code "151") (name "unconnected-(J7-Pad24)") (class "Default")
      (node (ref "J7") (pin "24") (pinfunction "24_24") (pintype "passive+no_connect"))
    )
    (net (code "152") (name "unconnected-(J7-Pad25)") (class "Default")
      (node (ref "J7") (pin "25") (pinfunction "25_25") (pintype "passive+no_connect"))
    )
    (net (code "153") (name "unconnected-(J7-Pad26)") (class "Default")
      (node (ref "J7") (pin "26") (pinfunction "26_26") (pintype "passive+no_connect"))
    )
    (net (code "154") (name "unconnected-(J7-Pad27)") (class "Default")
      (node (ref "J7") (pin "27") (pinfunction "27_27") (pintype "passive+no_connect"))
    )
    (net (code "155") (name "unconnected-(J7-Pad28)") (class "Default")
      (node (ref "J7") (pin "28") (pinfunction "28_28") (pintype "passive+no_connect"))
    )
    (net (code "156") (name "unconnected-(J7-Pad29)") (class "Default")
      (node (ref "J7") (pin "29") (pinfunction "29_29") (pintype "passive+no_connect"))
    )
    (net (code "157") (name "unconnected-(J7-Pad30)") (class "Default")
      (node (ref "J7") (pin "30") (pinfunction "30_30") (pintype "passive+no_connect"))
    )
    (net (code "158") (name "unconnected-(J7-Pad31)") (class "Default")
      (node (ref "J7") (pin "31") (pinfunction "31_31") (pintype "passive+no_connect"))
    )
    (net (code "159") (name "unconnected-(J7-Pad34)") (class "Default")
      (node (ref "J7") (pin "34") (pinfunction "34_34") (pintype "passive+no_connect"))
    )
    (net (code "160") (name "unconnected-(J7-Pad35)") (class "Default")
      (node (ref "J7") (pin "35") (pinfunction "35_35") (pintype "passive+no_connect"))
    )
    (net (code "161") (name "unconnected-(J7-Pad36)") (class "Default")
      (node (ref "J7") (pin "36") (pinfunction "36_36") (pintype "passive+no_connect"))
    )
    (net (code "162") (name "unconnected-(J7-Pad37)") (class "Default")
      (node (ref "J7") (pin "37") (pinfunction "37_37") (pintype "passive+no_connect"))
    )
    (net (code "163") (name "unconnected-(J7-Pad38)") (class "Default")
      (node (ref "J7") (pin "38") (pinfunction "38_38") (pintype "passive+no_connect"))
    )
    (net (code "164") (name "unconnected-(J7-Pad39)") (class "Default")
      (node (ref "J7") (pin "39") (pinfunction "39_39") (pintype "passive+no_connect"))
    )
    (net (code "165") (name "unconnected-(J7-Pad40)") (class "Default")
      (node (ref "J7") (pin "40") (pinfunction "40_40") (pintype "passive+no_connect"))
    )
    (net (code "166") (name "unconnected-(J7-Pad41)") (class "Default")
      (node (ref "J7") (pin "41") (pinfunction "41_41") (pintype "passive+no_connect"))
    )
    (net (code "167") (name "unconnected-(J7-Pad44)") (class "Default")
      (node (ref "J7") (pin "44") (pinfunction "44_44") (pintype "passive+no_connect"))
    )
    (net (code "168") (name "unconnected-(J7-Pad45)") (class "Default")
      (node (ref "J7") (pin "45") (pinfunction "45_45") (pintype "passive+no_connect"))
    )
    (net (code "169") (name "unconnected-(J7-Pad46)") (class "Default")
      (node (ref "J7") (pin "46") (pinfunction "46_46") (pintype "passive+no_connect"))
    )
    (net (code "170") (name "unconnected-(J7-Pad47)") (class "Default")
      (node (ref "J7") (pin "47") (pinfunction "47_47") (pintype "passive+no_connect"))
    )
    (net (code "171") (name "unconnected-(J7-Pad48)") (class "Default")
      (node (ref "J7") (pin "48") (pinfunction "48_48") (pintype "passive+no_connect"))
    )
    (net (code "172") (name "unconnected-(J7-Pad49)") (class "Default")
      (node (ref "J7") (pin "49") (pinfunction "49_49") (pintype "passive+no_connect"))
    )
    (net (code "173") (name "unconnected-(J7-Pad50)") (class "Default")
      (node (ref "J7") (pin "50") (pinfunction "50_50") (pintype "passive+no_connect"))
    )
    (net (code "174") (name "unconnected-(J7-Pad51)") (class "Default")
      (node (ref "J7") (pin "51") (pinfunction "51_51") (pintype "passive+no_connect"))
    )
    (net (code "175") (name "unconnected-(J7-Pad54)") (class "Default")
      (node (ref "J7") (pin "54") (pinfunction "54_54") (pintype "passive+no_connect"))
    )
    (net (code "176") (name "unconnected-(J7-Pad55)") (class "Default")
      (node (ref "J7") (pin "55") (pinfunction "55_55") (pintype "passive+no_connect"))
    )
    (net (code "177") (name "unconnected-(J7-Pad56)") (class "Default")
      (node (ref "J7") (pin "56") (pinfunction "56_56") (pintype "passive+no_connect"))
    )
    (net (code "178") (name "unconnected-(J7-Pad57)") (class "Default")
      (node (ref "J7") (pin "57") (pinfunction "57_57") (pintype "passive+no_connect"))
    )
    (net (code "179") (name "unconnected-(J7-Pad58)") (class "Default")
      (node (ref "J7") (pin "58") (pinfunction "58_58") (pintype "passive+no_connect"))
    )
    (net (code "180") (name "unconnected-(J7-Pad61)") (class "Default")
      (node (ref "J7") (pin "61") (pinfunction "61_61") (pintype "passive+no_connect"))
    )
    (net (code "181") (name "unconnected-(J7-Pad62)") (class "Default")
      (node (ref "J7") (pin "62") (pinfunction "62_62") (pintype "passive+no_connect"))
    )
    (net (code "182") (name "unconnected-(J7-Pad63)") (class "Default")
      (node (ref "J7") (pin "63") (pinfunction "63_63") (pintype "passive+no_connect"))
    )
    (net (code "183") (name "unconnected-(J7-Pad64)") (class "Default")
      (node (ref "J7") (pin "64") (pinfunction "64_64") (pintype "passive+no_connect"))
    )
    (net (code "184") (name "unconnected-(J7-Pad67)") (class "Default")
      (node (ref "J7") (pin "67") (pinfunction "67_67") (pintype "passive+no_connect"))
    )
    (net (code "185") (name "unconnected-(J7-Pad68)") (class "Default")
      (node (ref "J7") (pin "68") (pinfunction "68_68") (pintype "passive+no_connect"))
    )
    (net (code "186") (name "unconnected-(J7-Pad69)") (class "Default")
      (node (ref "J7") (pin "69") (pinfunction "69_69") (pintype "passive+no_connect"))
    )
    (net (code "187") (name "unconnected-(J7-Pad70)") (class "Default")
      (node (ref "J7") (pin "70") (pinfunction "70_70") (pintype "passive+no_connect"))
    )
    (net (code "188") (name "unconnected-(J7-Pad72)") (class "Default")
      (node (ref "J7") (pin "72") (pinfunction "72_72") (pintype "passive+no_connect"))
    )
    (net (code "189") (name "unconnected-(J7-Pad73)") (class "Default")
      (node (ref "J7") (pin "73") (pinfunction "73_73") (pintype "passive+no_connect"))
    )
    (net (code "190") (name "unconnected-(J7-Pad75)") (class "Default")
      (node (ref "J7") (pin "75") (pinfunction "75_75") (pintype "passive+no_connect"))
    )
    (net (code "191") (name "unconnected-(J7-Pad76)") (class "Default")
      (node (ref "J7") (pin "76") (pinfunction "76_76") (pintype "passive+no_connect"))
    )
    (net (code "192") (name "unconnected-(J7-Pad77)") (class "Default")
      (node (ref "J7") (pin "77") (pinfunction "77_77") (pintype "passive+no_connect"))
    )
    (net (code "193") (name "unconnected-(J7-Pad78)") (class "Default")
      (node (ref "J7") (pin "78") (pinfunction "78_78") (pintype "passive+no_connect"))
    )
    (net (code "194") (name "unconnected-(J7-Pad79)") (class "Default")
      (node (ref "J7") (pin "79") (pinfunction "79_79") (pintype "passive+no_connect"))
    )
    (net (code "195") (name "unconnected-(J7-Pad80)") (class "Default")
      (node (ref "J7") (pin "80") (pinfunction "80_80") (pintype "passive+no_connect"))
    )
    (net (code "196") (name "unconnected-(J7-Pad81)") (class "Default")
      (node (ref "J7") (pin "81") (pinfunction "81_81") (pintype "passive+no_connect"))
    )
    (net (code "197") (name "unconnected-(J7-Pad82)") (class "Default")
      (node (ref "J7") (pin "82") (pinfunction "82_82") (pintype "passive+no_connect"))
    )
    (net (code "198") (name "unconnected-(J7-Pad83)") (class "Default")
      (node (ref "J7") (pin "83") (pinfunction "83_83") (pintype "passive+no_connect"))
    )
    (net (code "199") (name "unconnected-(J7-Pad84)") (class "Default")
      (node (ref "J7") (pin "84") (pinfunction "84_84") (pintype "passive+no_connect"))
    )
    (net (code "200") (name "unconnected-(J7-Pad85)") (class "Default")
      (node (ref "J7") (pin "85") (pinfunction "85_85") (pintype "passive+no_connect"))
    )
    (net (code "201") (name "unconnected-(J7-Pad86)") (class "Default")
      (node (ref "J7") (pin "86") (pinfunction "86_86") (pintype "passive+no_connect"))
    )
    (net (code "202") (name "unconnected-(J7-Pad87)") (class "Default")
      (node (ref "J7") (pin "87") (pinfunction "87_87") (pintype "passive+no_connect"))
    )
    (net (code "203") (name "unconnected-(J7-Pad88)") (class "Default")
      (node (ref "J7") (pin "88") (pinfunction "88_88") (pintype "passive+no_connect"))
    )
    (net (code "204") (name "unconnected-(J7-Pad89)") (class "Default")
      (node (ref "J7") (pin "89") (pinfunction "89_89") (pintype "passive+no_connect"))
    )
    (net (code "205") (name "unconnected-(J7-Pad90)") (class "Default")
      (node (ref "J7") (pin "90") (pinfunction "90_90") (pintype "passive+no_connect"))
    )
    (net (code "206") (name "unconnected-(J7-Pad91)") (class "Default")
      (node (ref "J7") (pin "91") (pinfunction "91_91") (pintype "passive+no_connect"))
    )
    (net (code "207") (name "unconnected-(J7-Pad92)") (class "Default")
      (node (ref "J7") (pin "92") (pinfunction "92_92") (pintype "passive+no_connect"))
    )
    (net (code "208") (name "unconnected-(J7-Pad93)") (class "Default")
      (node (ref "J7") (pin "93") (pinfunction "93_93") (pintype "passive+no_connect"))
    )
    (net (code "209") (name "unconnected-(J7-Pad94)") (class "Default")
      (node (ref "J7") (pin "94") (pinfunction "94_94") (pintype "passive+no_connect"))
    )
    (net (code "210") (name "unconnected-(J7-Pad95)") (class "Default")
      (node (ref "J7") (pin "95") (pinfunction "95_95") (pintype "passive+no_connect"))
    )
    (net (code "211") (name "unconnected-(J7-Pad96)") (class "Default")
      (node (ref "J7") (pin "96") (pinfunction "96_96") (pintype "passive+no_connect"))
    )
    (net (code "212") (name "unconnected-(J7-Pad97)") (class "Default")
      (node (ref "J7") (pin "97") (pinfunction "97_97") (pintype "passive+no_connect"))
    )
    (net (code "213") (name "unconnected-(J7-Pad99)") (class "Default")
      (node (ref "J7") (pin "99") (pinfunction "99_99") (pintype "passive+no_connect"))
    )
    (net (code "214") (name "unconnected-(J7-Pad100)") (class "Default")
      (node (ref "J7") (pin "100") (pinfunction "100_100") (pintype "passive+no_connect"))
    )
    (net (code "215") (name "unconnected-(J8-Pad1)") (class "Default")
      (node (ref "J8") (pin "1") (pinfunction "1_1") (pintype "passive+no_connect"))
    )
    (net (code "216") (name "unconnected-(J8-Pad2)") (class "Default")
      (node (ref "J8") (pin "2") (pinfunction "2_2") (pintype "passive+no_connect"))
    )
    (net (code "217") (name "unconnected-(J8-Pad3)") (class "Default")
      (node (ref "J8") (pin "3") (pinfunction "3_3") (pintype "passive+no_connect"))
    )
    (net (code "218") (name "unconnected-(J8-Pad4)") (class "Default")
      (node (ref "J8") (pin "4") (pinfunction "4_4") (pintype "passive+no_connect"))
    )
    (net (code "219") (name "unconnected-(J8-Pad5)") (class "Default")
      (node (ref "J8") (pin "5") (pinfunction "5_5") (pintype "passive+no_connect"))
    )
    (net (code "220") (name "unconnected-(J8-Pad6)") (class "Default")
      (node (ref "J8") (pin "6") (pinfunction "6_6") (pintype "passive+no_connect"))
    )
    (net (code "221") (name "unconnected-(J8-Pad9)") (class "Default")
      (node (ref "J8") (pin "9") (pinfunction "9_9") (pintype "passive+no_connect"))
    )
    (net (code "222") (name "unconnected-(J8-Pad10)") (class "Default")
      (node (ref "J8") (pin "10") (pinfunction "10_10") (pintype "passive+no_connect"))
    )
    (net (code "223") (name "unconnected-(J8-Pad11)") (class "Default")
      (node (ref "J8") (pin "11") (pinfunction "11_11") (pintype "passive+no_connect"))
    )
    (net (code "224") (name "unconnected-(J8-Pad12)") (class "Default")
      (node (ref "J8") (pin "12") (pinfunction "12_12") (pintype "passive+no_connect"))
    )
    (net (code "225") (name "unconnected-(J8-Pad15)") (class "Default")
      (node (ref "J8") (pin "15") (pinfunction "15_15") (pintype "passive+no_connect"))
    )
    (net (code "226") (name "unconnected-(J8-Pad16)") (class "Default")
      (node (ref "J8") (pin "16") (pinfunction "16_16") (pintype "passive+no_connect"))
    )
    (net (code "227") (name "unconnected-(J8-Pad17)") (class "Default")
      (node (ref "J8") (pin "17") (pinfunction "17_17") (pintype "passive+no_connect"))
    )
    (net (code "228") (name "unconnected-(J8-Pad18)") (class "Default")
      (node (ref "J8") (pin "18") (pinfunction "18_18") (pintype "passive+no_connect"))
    )
    (net (code "229") (name "unconnected-(J8-Pad21)") (class "Default")
      (node (ref "J8") (pin "21") (pinfunction "21_21") (pintype "passive+no_connect"))
    )
    (net (code "230") (name "unconnected-(J8-Pad22)") (class "Default")
      (node (ref "J8") (pin "22") (pinfunction "22_22") (pintype "passive+no_connect"))
    )
    (net (code "231") (name "unconnected-(J8-Pad23)") (class "Default")
      (node (ref "J8") (pin "23") (pinfunction "23_23") (pintype "passive+no_connect"))
    )
    (net (code "232") (name "unconnected-(J8-Pad24)") (class "Default")
      (node (ref "J8") (pin "24") (pinfunction "24_24") (pintype "passive+no_connect"))
    )
    (net (code "233") (name "unconnected-(J8-Pad27)") (class "Default")
      (node (ref "J8") (pin "27") (pinfunction "27_27") (pintype "passive+no_connect"))
    )
    (net (code "234") (name "unconnected-(J8-Pad28)") (class "Default")
      (node (ref "J8") (pin "28") (pinfunction "28_28") (pintype "passive+no_connect"))
    )
    (net (code "235") (name "unconnected-(J8-Pad29)") (class "Default")
      (node (ref "J8") (pin "29") (pinfunction "29_29") (pintype "passive+no_connect"))
    )
    (net (code "236") (name "unconnected-(J8-Pad30)") (class "Default")
      (node (ref "J8") (pin "30") (pinfunction "30_30") (pintype "passive+no_connect"))
    )
    (net (code "237") (name "unconnected-(J8-Pad33)") (class "Default")
      (node (ref "J8") (pin "33") (pinfunction "33_33") (pintype "passive+no_connect"))
    )
    (net (code "238") (name "unconnected-(J8-Pad34)") (class "Default")
      (node (ref "J8") (pin "34") (pinfunction "34_34") (pintype "passive+no_connect"))
    )
    (net (code "239") (name "unconnected-(J8-Pad35)") (class "Default")
      (node (ref "J8") (pin "35") (pinfunction "35_35") (pintype "passive+no_connect"))
    )
    (net (code "240") (name "unconnected-(J8-Pad36)") (class "Default")
      (node (ref "J8") (pin "36") (pinfunction "36_36") (pintype "passive+no_connect"))
    )
    (net (code "241") (name "unconnected-(J8-Pad39)") (class "Default")
      (node (ref "J8") (pin "39") (pinfunction "39_39") (pintype "passive+no_connect"))
    )
    (net (code "242") (name "unconnected-(J8-Pad40)") (class "Default")
      (node (ref "J8") (pin "40") (pinfunction "40_40") (pintype "passive+no_connect"))
    )
    (net (code "243") (name "unconnected-(J8-Pad41)") (class "Default")
      (node (ref "J8") (pin "41") (pinfunction "41_41") (pintype "passive+no_connect"))
    )
    (net (code "244") (name "unconnected-(J8-Pad42)") (class "Default")
      (node (ref "J8") (pin "42") (pinfunction "42_42") (pintype "passive+no_connect"))
    )
    (net (code "245") (name "unconnected-(J8-Pad43)") (class "Default")
      (node (ref "J8") (pin "43") (pinfunction "43_43") (pintype "passive+no_connect"))
    )
    (net (code "246") (name "unconnected-(J8-Pad45)") (class "Default")
      (node (ref "J8") (pin "45") (pinfunction "45_45") (pintype "passive+no_connect"))
    )
    (net (code "247") (name "unconnected-(J8-Pad46)") (class "Default")
      (node (ref "J8") (pin "46") (pinfunction "46_46") (pintype "passive+no_connect"))
    )
    (net (code "248") (name "unconnected-(J8-Pad47)") (class "Default")
      (node (ref "J8") (pin "47") (pinfunction "47_47") (pintype "passive+no_connect"))
    )
    (net (code "249") (name "unconnected-(J8-Pad48)") (class "Default")
      (node (ref "J8") (pin "48") (pinfunction "48_48") (pintype "passive+no_connect"))
    )
    (net (code "250") (name "unconnected-(J8-Pad49)") (class "Default")
      (node (ref "J8") (pin "49") (pinfunction "49_49") (pintype "passive+no_connect"))
    )
    (net (code "251") (name "unconnected-(J8-Pad51)") (class "Default")
      (node (ref "J8") (pin "51") (pinfunction "51_51") (pintype "passive+no_connect"))
    )
    (net (code "252") (name "unconnected-(J8-Pad52)") (class "Default")
      (node (ref "J8") (pin "52") (pinfunction "52_52") (pintype "passive+no_connect"))
    )
    (net (code "253") (name "unconnected-(J8-Pad53)") (class "Default")
      (node (ref "J8") (pin "53") (pinfunction "53_53") (pintype "passive+no_connect"))
    )
    (net (code "254") (name "unconnected-(J8-Pad54)") (class "Default")
      (node (ref "J8") (pin "54") (pinfunction "54_54") (pintype "passive+no_connect"))
    )
    (net (code "255") (name "unconnected-(J8-Pad57)") (class "Default")
      (node (ref "J8") (pin "57") (pinfunction "57_57") (pintype "passive+no_connect"))
    )
    (net (code "256") (name "unconnected-(J8-Pad58)") (class "Default")
      (node (ref "J8") (pin "58") (pinfunction "58_58") (pintype "passive+no_connect"))
    )
    (net (code "257") (name "unconnected-(J8-Pad59)") (class "Default")
      (node (ref "J8") (pin "59") (pinfunction "59_59") (pintype "passive+no_connect"))
    )
    (net (code "258") (name "unconnected-(J8-Pad60)") (class "Default")
      (node (ref "J8") (pin "60") (pinfunction "60_60") (pintype "passive+no_connect"))
    )
    (net (code "259") (name "unconnected-(J8-Pad63)") (class "Default")
      (node (ref "J8") (pin "63") (pinfunction "63_63") (pintype "passive+no_connect"))
    )
    (net (code "260") (name "unconnected-(J8-Pad64)") (class "Default")
      (node (ref "J8") (pin "64") (pinfunction "64_64") (pintype "passive+no_connect"))
    )
    (net (code "261") (name "unconnected-(J8-Pad65)") (class "Default")
      (node (ref "J8") (pin "65") (pinfunction "65_65") (pintype "passive+no_connect"))
    )
    (net (code "262") (name "unconnected-(J8-Pad66)") (class "Default")
      (node (ref "J8") (pin "66") (pinfunction "66_66") (pintype "passive+no_connect"))
    )
    (net (code "263") (name "unconnected-(J8-Pad69)") (class "Default")
      (node (ref "J8") (pin "69") (pinfunction "69_69") (pintype "passive+no_connect"))
    )
    (net (code "264") (name "unconnected-(J8-Pad70)") (class "Default")
      (node (ref "J8") (pin "70") (pinfunction "70_70") (pintype "passive+no_connect"))
    )
    (net (code "265") (name "unconnected-(J8-Pad71)") (class "Default")
      (node (ref "J8") (pin "71") (pinfunction "71_71") (pintype "passive+no_connect"))
    )
    (net (code "266") (name "unconnected-(J8-Pad72)") (class "Default")
      (node (ref "J8") (pin "72") (pinfunction "72_72") (pintype "passive+no_connect"))
    )
    (net (code "267") (name "unconnected-(J8-Pad75)") (class "Default")
      (node (ref "J8") (pin "75") (pinfunction "75_75") (pintype "passive+no_connect"))
    )
    (net (code "268") (name "unconnected-(J8-Pad76)") (class "Default")
      (node (ref "J8") (pin "76") (pinfunction "76_76") (pintype "passive+no_connect"))
    )
    (net (code "269") (name "unconnected-(J8-Pad77)") (class "Default")
      (node (ref "J8") (pin "77") (pinfunction "77_77") (pintype "passive+no_connect"))
    )
    (net (code "270") (name "unconnected-(J8-Pad78)") (class "Default")
      (node (ref "J8") (pin "78") (pinfunction "78_78") (pintype "passive+no_connect"))
    )
    (net (code "271") (name "unconnected-(J8-Pad81)") (class "Default")
      (node (ref "J8") (pin "81") (pinfunction "81_81") (pintype "passive+no_connect"))
    )
    (net (code "272") (name "unconnected-(J8-Pad82)") (class "Default")
      (node (ref "J8") (pin "82") (pinfunction "82_82") (pintype "passive+no_connect"))
    )
    (net (code "273") (name "unconnected-(J8-Pad83)") (class "Default")
      (node (ref "J8") (pin "83") (pinfunction "83_83") (pintype "passive+no_connect"))
    )
    (net (code "274") (name "unconnected-(J8-Pad84)") (class "Default")
      (node (ref "J8") (pin "84") (pinfunction "84_84") (pintype "passive+no_connect"))
    )
    (net (code "275") (name "unconnected-(J8-Pad87)") (class "Default")
      (node (ref "J8") (pin "87") (pinfunction "87_87") (pintype "passive+no_connect"))
    )
    (net (code "276") (name "unconnected-(J8-Pad88)") (class "Default")
      (node (ref "J8") (pin "88") (pinfunction "88_88") (pintype "passive+no_connect"))
    )
    (net (code "277") (name "unconnected-(J8-Pad89)") (class "Default")
      (node (ref "J8") (pin "89") (pinfunction "89_89") (pintype "passive+no_connect"))
    )
    (net (code "278") (name "unconnected-(J8-Pad90)") (class "Default")
      (node (ref "J8") (pin "90") (pinfunction "90_90") (pintype "passive+no_connect"))
    )
    (net (code "279") (name "unconnected-(J8-Pad93)") (class "Default")
      (node (ref "J8") (pin "93") (pinfunction "93_93") (pintype "passive+no_connect"))
    )
    (net (code "280") (name "unconnected-(J8-Pad94)") (class "Default")
      (node (ref "J8") (pin "94") (pinfunction "94_94") (pintype "passive+no_connect"))
    )
    (net (code "281") (name "unconnected-(J8-Pad95)") (class "Default")
      (node (ref "J8") (pin "95") (pinfunction "95_95") (pintype "passive+no_connect"))
    )
    (net (code "282") (name "unconnected-(J8-Pad96)") (class "Default")
      (node (ref "J8") (pin "96") (pinfunction "96_96") (pintype "passive+no_connect"))
    )
    (net (code "283") (name "unconnected-(J8-Pad99)") (class "Default")
      (node (ref "J8") (pin "99") (pinfunction "99_99") (pintype "passive+no_connect"))
    )
    (net (code "284") (name "unconnected-(J8-Pad100)") (class "Default")
      (node (ref "J8") (pin "100") (pinfunction "100_100") (pintype "passive+no_connect"))
    )
  )
)
